# SERVO_DRIVER.net
KiCad netlist of a schematic drawn in Altium Designer
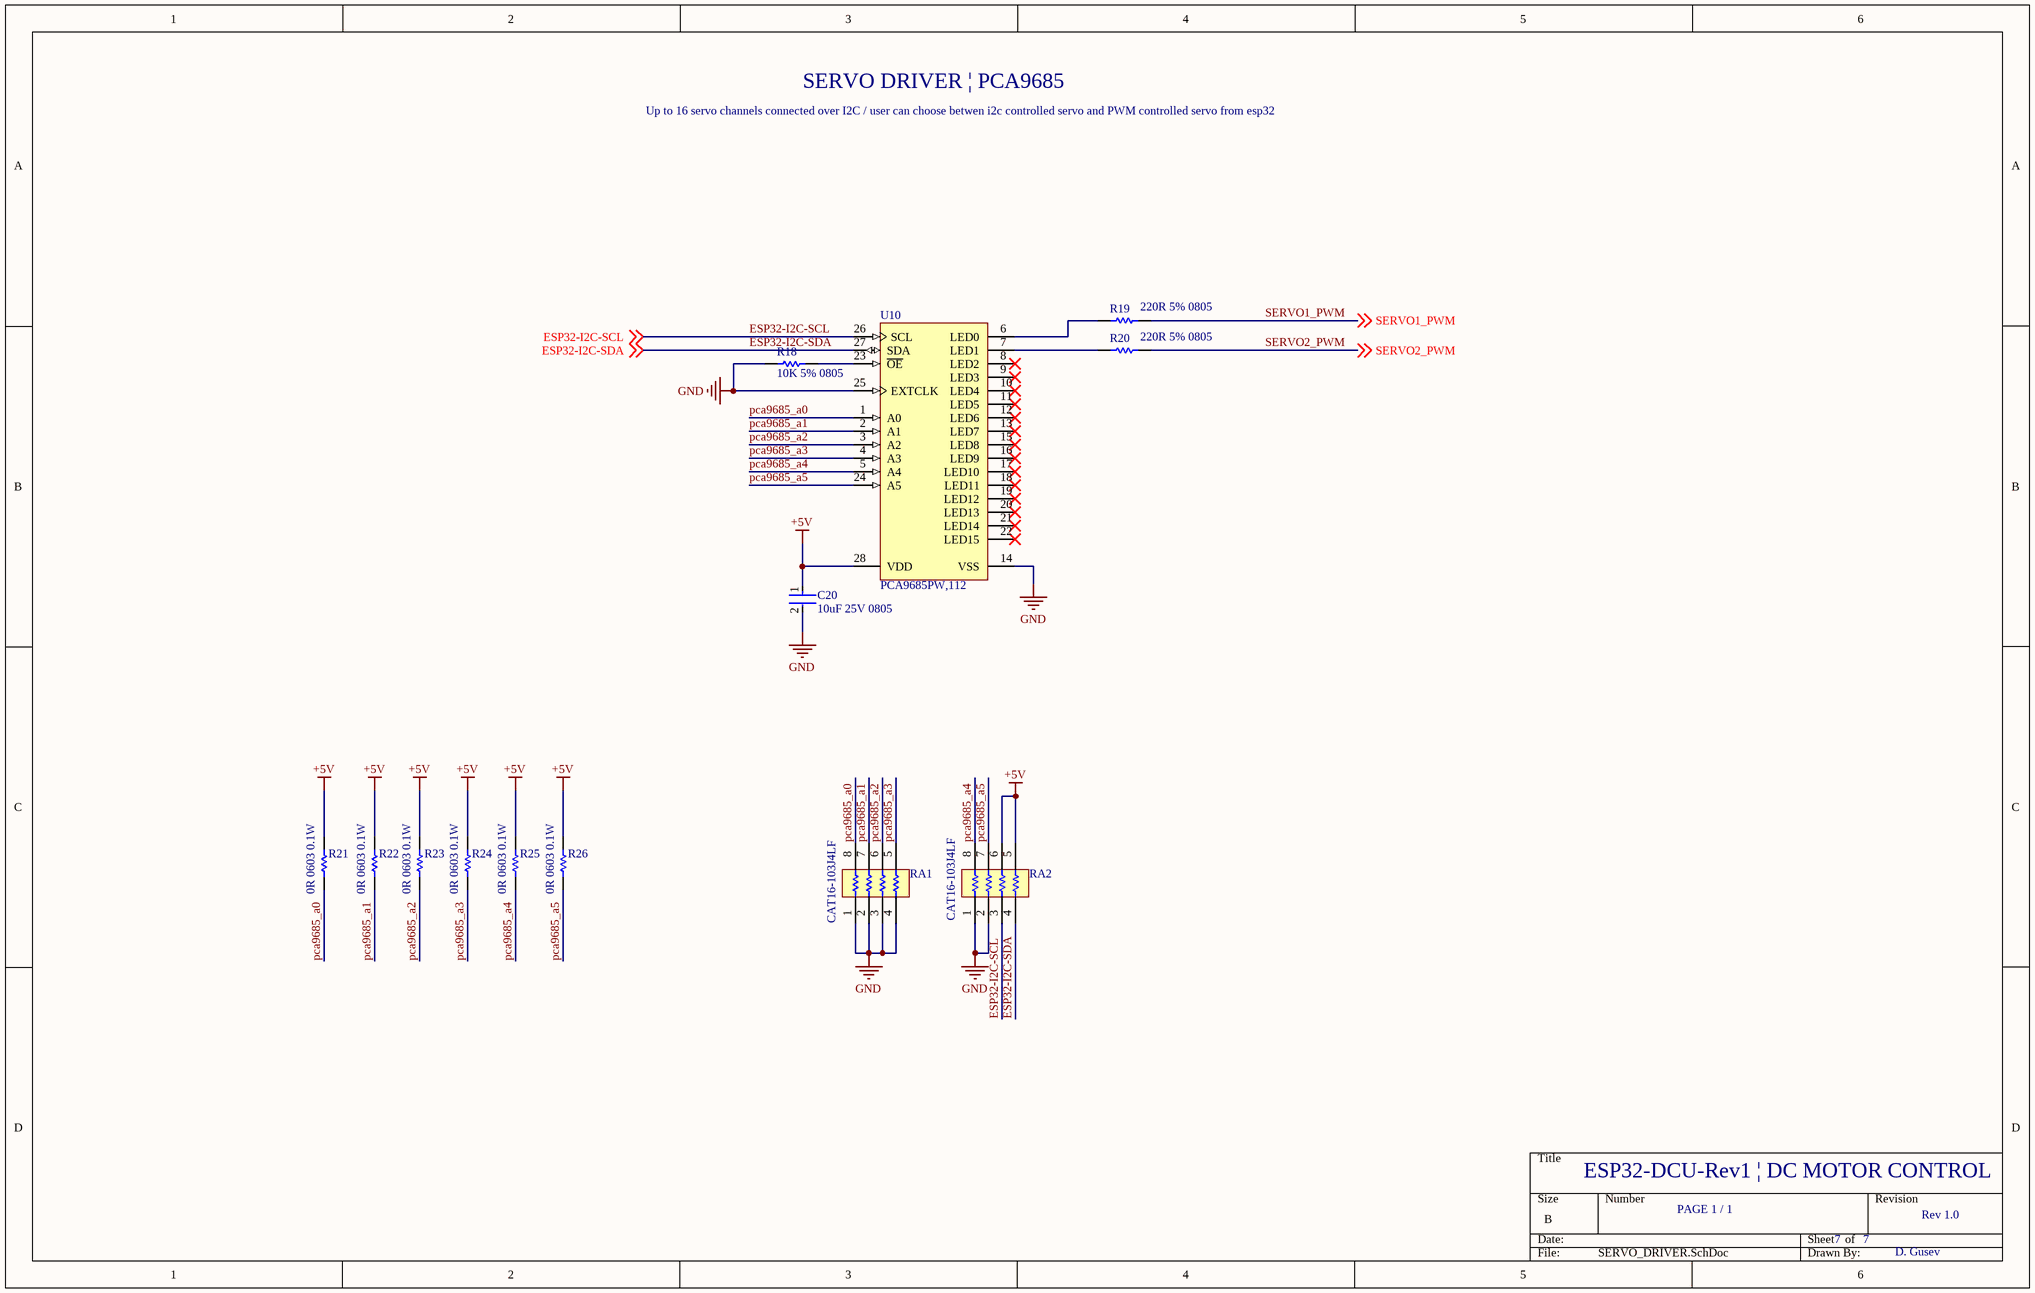
[diagram p0: SERVO_DRIVER.SchDoc]

(export (version "E")
  (design (tool "Eeschema 10.0.6"))
  (components
    (comp (ref "C20")
      (value "10uF 25V 0805")
      (footprint "FP-GRM21B-0_15-IPC_C")
      (description "Chip Multilayer Ceramic Capacitors for General Purpose, 0805, 10uF, X5R, 15%, 10%, 25V")
      (fields (field (name "VOLTAGE") "25V") (field (name "TOLERANCE") "10%"))
      (libsource (lib "Altium Content Vault") (part "b4654b650e69147ec39a6b967a45e02"))
    )
    (comp (ref "R18")
      (value "10K 5% 0805")
      (footprint "RESC2013X60X35NL10T20")
      (description "Chip Resistor, 10 KOhm, +/- 1%, 0.125 W, -55 to 155 degC, 0805 (2012 Metric), RoHS, Tape and Reel")
      (fields (field (name "MANUFACTURER") "Yageo"))
      (libsource (lib "Altium Content Vault") (part "RES-2"))
    )
    (comp (ref "R19")
      (value "220R 5% 0805")
      (footprint "RESC2013X60X40NL20T25")
      (fields (field (name "MANUFACTURER") "Panasonic") (field (name "PART NUMBER") "ERA6AEB221V"))
      (libsource (lib "Altium Content Vault") (part "RES"))
    )
    (comp (ref "R20")
      (value "220R 5% 0805")
      (footprint "RESC2013X60X40NL20T25")
      (fields (field (name "MANUFACTURER") "Panasonic") (field (name "PART NUMBER") "ERA6AEB221V"))
      (libsource (lib "Altium Content Vault") (part "RES"))
    )
    (comp (ref "R21")
      (value "0R 0603 0.1W")
      (footprint "RESC1608X55X25ML10T15")
      (description "Chip Resistor, 0 Ohm, +/- 5%, 0.1 W, -55 to 155 degC, 0603 (1608 Metric), RoHS, Tape and Reel")
      (fields (field (name "TOLERANCE") "5%") (field (name "MANUFACTURER") "Yageo"))
      (libsource (lib "Altium Content Vault") (part "RES-2"))
    )
    (comp (ref "R22")
      (value "0R 0603 0.1W")
      (footprint "RESC1608X55X25ML10T15")
      (description "Chip Resistor, 0 Ohm, +/- 5%, 0.1 W, -55 to 155 degC, 0603 (1608 Metric), RoHS, Tape and Reel")
      (fields (field (name "TOLERANCE") "5%") (field (name "MANUFACTURER") "Yageo"))
      (libsource (lib "Altium Content Vault") (part "RES-2"))
    )
    (comp (ref "R23")
      (value "0R 0603 0.1W")
      (footprint "RESC1608X55X25ML10T15")
      (description "Chip Resistor, 0 Ohm, +/- 5%, 0.1 W, -55 to 155 degC, 0603 (1608 Metric), RoHS, Tape and Reel")
      (fields (field (name "TOLERANCE") "5%") (field (name "MANUFACTURER") "Yageo"))
      (libsource (lib "Altium Content Vault") (part "RES-2"))
    )
    (comp (ref "R24")
      (value "0R 0603 0.1W")
      (footprint "RESC1608X55X25ML10T15")
      (description "Chip Resistor, 0 Ohm, +/- 5%, 0.1 W, -55 to 155 degC, 0603 (1608 Metric), RoHS, Tape and Reel")
      (fields (field (name "TOLERANCE") "5%") (field (name "MANUFACTURER") "Yageo"))
      (libsource (lib "Altium Content Vault") (part "RES-2"))
    )
    (comp (ref "R25")
      (value "0R 0603 0.1W")
      (footprint "RESC1608X55X25ML10T15")
      (description "Chip Resistor, 0 Ohm, +/- 5%, 0.1 W, -55 to 155 degC, 0603 (1608 Metric), RoHS, Tape and Reel")
      (fields (field (name "TOLERANCE") "5%") (field (name "MANUFACTURER") "Yageo"))
      (libsource (lib "Altium Content Vault") (part "RES-2"))
    )
    (comp (ref "R26")
      (value "0R 0603 0.1W")
      (footprint "RESC1608X55X25ML10T15")
      (description "Chip Resistor, 0 Ohm, +/- 5%, 0.1 W, -55 to 155 degC, 0603 (1608 Metric), RoHS, Tape and Reel")
      (fields (field (name "TOLERANCE") "5%") (field (name "MANUFACTURER") "Yageo"))
      (libsource (lib "Altium Content Vault") (part "RES-2"))
    )
    (comp (ref "RA1")
      (value "CAT16-103J4LF")
      (footprint "BOUR-CAT16-103J4LF_L")
      (fields (field (name "MANUFACTURER") "Bourns") (field (name "TOLERANCE") "±5%"))
      (libsource (lib "Altium Content Vault") (part "RES-P-8"))
    )
    (comp (ref "RA2")
      (value "CAT16-103J4LF")
      (footprint "BOUR-CAT16-103J4LF_L")
      (fields (field (name "MANUFACTURER") "Bourns") (field (name "TOLERANCE") "±5%"))
      (libsource (lib "Altium Content Vault") (part "RES-P-8"))
    )
    (comp (ref "U10")
      (value "PCA9685PW,112")
      (footprint "SOT361-1_V")
      (fields (field (name "PARTNUMBER") "PCA9685"))
      (libsource (lib "Altium Content Vault") (part "NXP-PCA9685-SOT361-1"))
    )
  )
  (nets
    (net (code "1") (name "+5V") (class "Default")
      (node (ref "C20") (pin "1") (pinfunction "1_1") (pintype "passive"))
      (node (ref "R21") (pin "2") (pinfunction "2_2") (pintype "passive"))
      (node (ref "R22") (pin "2") (pinfunction "2_2") (pintype "passive"))
      (node (ref "R23") (pin "2") (pinfunction "2_2") (pintype "passive"))
      (node (ref "R24") (pin "2") (pinfunction "2_2") (pintype "passive"))
      (node (ref "R25") (pin "2") (pinfunction "2_2") (pintype "passive"))
      (node (ref "R26") (pin "2") (pinfunction "2_2") (pintype "passive"))
      (node (ref "RA2") (pin "5") (pinfunction "5_5") (pintype "passive"))
      (node (ref "RA2") (pin "6") (pinfunction "6_6") (pintype "passive"))
      (node (ref "U10") (pin "28") (pinfunction "VDD_28") (pintype "power_in"))
    )
    (net (code "2") (name "/pca9685_a0") (class "Default")
      (node (ref "R21") (pin "1") (pinfunction "1_1") (pintype "passive"))
      (node (ref "RA1") (pin "8") (pinfunction "8_8") (pintype "passive"))
      (node (ref "U10") (pin "1") (pinfunction "A0_1") (pintype "input"))
    )
    (net (code "3") (name "/pca9685_a1") (class "Default")
      (node (ref "R22") (pin "1") (pinfunction "1_1") (pintype "passive"))
      (node (ref "RA1") (pin "7") (pinfunction "7_7") (pintype "passive"))
      (node (ref "U10") (pin "2") (pinfunction "A1_2") (pintype "input"))
    )
    (net (code "4") (name "/pca9685_a2") (class "Default")
      (node (ref "R23") (pin "1") (pinfunction "1_1") (pintype "passive"))
      (node (ref "RA1") (pin "6") (pinfunction "6_6") (pintype "passive"))
      (node (ref "U10") (pin "3") (pinfunction "A2_3") (pintype "input"))
    )
    (net (code "5") (name "/pca9685_a3") (class "Default")
      (node (ref "R24") (pin "1") (pinfunction "1_1") (pintype "passive"))
      (node (ref "RA1") (pin "5") (pinfunction "5_5") (pintype "passive"))
      (node (ref "U10") (pin "4") (pinfunction "A3_4") (pintype "input"))
    )
    (net (code "6") (name "/pca9685_a4") (class "Default")
      (node (ref "R25") (pin "1") (pinfunction "1_1") (pintype "passive"))
      (node (ref "RA2") (pin "8") (pinfunction "8_8") (pintype "passive"))
      (node (ref "U10") (pin "5") (pinfunction "A4_5") (pintype "input"))
    )
    (net (code "7") (name "/pca9685_a5") (class "Default")
      (node (ref "R26") (pin "1") (pinfunction "1_1") (pintype "passive"))
      (node (ref "RA2") (pin "7") (pinfunction "7_7") (pintype "passive"))
      (node (ref "U10") (pin "24") (pinfunction "A5_24") (pintype "input"))
    )
    (net (code "8") (name "ESP32-I2C-SCL") (class "Default")
      (node (ref "RA2") (pin "3") (pinfunction "3_3") (pintype "passive"))
      (node (ref "U10") (pin "26") (pinfunction "SCL_26") (pintype "input"))
    )
    (net (code "9") (name "ESP32-I2C-SDA") (class "Default")
      (node (ref "RA2") (pin "4") (pinfunction "4_4") (pintype "passive"))
      (node (ref "U10") (pin "27") (pinfunction "SDA_27") (pintype "bidirectional"))
    )
    (net (code "10") (name "GND") (class "Default")
      (node (ref "C20") (pin "2") (pinfunction "2_2") (pintype "passive"))
      (node (ref "R18") (pin "2") (pinfunction "2_2") (pintype "passive"))
      (node (ref "RA1") (pin "1") (pinfunction "1_1") (pintype "passive"))
      (node (ref "RA1") (pin "2") (pinfunction "2_2") (pintype "passive"))
      (node (ref "RA1") (pin "3") (pinfunction "3_3") (pintype "passive"))
      (node (ref "RA1") (pin "4") (pinfunction "4_4") (pintype "passive"))
      (node (ref "RA2") (pin "1") (pinfunction "1_1") (pintype "passive"))
      (node (ref "RA2") (pin "2") (pinfunction "2_2") (pintype "passive"))
      (node (ref "U10") (pin "14") (pinfunction "VSS_14") (pintype "power_in"))
      (node (ref "U10") (pin "25") (pinfunction "EXTCLK_25") (pintype "input"))
    )
    (net (code "11") (name "Net-(U10-LED0)") (class "Default")
      (node (ref "R19") (pin "1") (pinfunction "1_1") (pintype "passive"))
      (node (ref "U10") (pin "6") (pinfunction "LED0_6") (pintype "tri_state"))
    )
    (net (code "12") (name "Net-(U10-LED1)") (class "Default")
      (node (ref "R20") (pin "1") (pinfunction "1_1") (pintype "passive"))
      (node (ref "U10") (pin "7") (pinfunction "LED1_7") (pintype "tri_state"))
    )
    (net (code "13") (name "Net-(U10-~{OE})") (class "Default")
      (node (ref "R18") (pin "1") (pinfunction "1_1") (pintype "passive"))
      (node (ref "U10") (pin "23") (pinfunction "~{OE}_23") (pintype "input"))
    )
    (net (code "14") (name "SERVO1_PWM") (class "Default")
      (node (ref "R19") (pin "2") (pinfunction "2_2") (pintype "passive"))
    )
    (net (code "15") (name "SERVO2_PWM") (class "Default")
      (node (ref "R20") (pin "2") (pinfunction "2_2") (pintype "passive"))
    )
    (net (code "16") (name "unconnected-(U10-LED2-Pad8)") (class "Default")
      (node (ref "U10") (pin "8") (pinfunction "LED2_8") (pintype "tri_state+no_connect"))
    )
    (net (code "17") (name "unconnected-(U10-LED3-Pad9)") (class "Default")
      (node (ref "U10") (pin "9") (pinfunction "LED3_9") (pintype "tri_state+no_connect"))
    )
    (net (code "18") (name "unconnected-(U10-LED4-Pad10)") (class "Default")
      (node (ref "U10") (pin "10") (pinfunction "LED4_10") (pintype "tri_state+no_connect"))
    )
    (net (code "19") (name "unconnected-(U10-LED5-Pad11)") (class "Default")
      (node (ref "U10") (pin "11") (pinfunction "LED5_11") (pintype "tri_state+no_connect"))
    )
    (net (code "20") (name "unconnected-(U10-LED6-Pad12)") (class "Default")
      (node (ref "U10") (pin "12") (pinfunction "LED6_12") (pintype "tri_state+no_connect"))
    )
    (net (code "21") (name "unconnected-(U10-LED7-Pad13)") (class "Default")
      (node (ref "U10") (pin "13") (pinfunction "LED7_13") (pintype "tri_state+no_connect"))
    )
    (net (code "22") (name "unconnected-(U10-LED8-Pad15)") (class "Default")
      (node (ref "U10") (pin "15") (pinfunction "LED8_15") (pintype "tri_state+no_connect"))
    )
    (net (code "23") (name "unconnected-(U10-LED9-Pad16)") (class "Default")
      (node (ref "U10") (pin "16") (pinfunction "LED9_16") (pintype "tri_state+no_connect"))
    )
    (net (code "24") (name "unconnected-(U10-LED10-Pad17)") (class "Default")
      (node (ref "U10") (pin "17") (pinfunction "LED10_17") (pintype "tri_state+no_connect"))
    )
    (net (code "25") (name "unconnected-(U10-LED11-Pad18)") (class "Default")
      (node (ref "U10") (pin "18") (pinfunction "LED11_18") (pintype "tri_state+no_connect"))
    )
    (net (code "26") (name "unconnected-(U10-LED12-Pad19)") (class "Default")
      (node (ref "U10") (pin "19") (pinfunction "LED12_19") (pintype "tri_state+no_connect"))
    )
    (net (code "27") (name "unconnected-(U10-LED13-Pad20)") (class "Default")
      (node (ref "U10") (pin "20") (pinfunction "LED13_20") (pintype "tri_state+no_connect"))
    )
    (net (code "28") (name "unconnected-(U10-LED14-Pad21)") (class "Default")
      (node (ref "U10") (pin "21") (pinfunction "LED14_21") (pintype "tri_state+no_connect"))
    )
    (net (code "29") (name "unconnected-(U10-LED15-Pad22)") (class "Default")
      (node (ref "U10") (pin "22") (pinfunction "LED15_22") (pintype "tri_state+no_connect"))
    )
  )
)
